# High_Side_FETs.net
KiCad netlist of a schematic drawn in Altium Designer
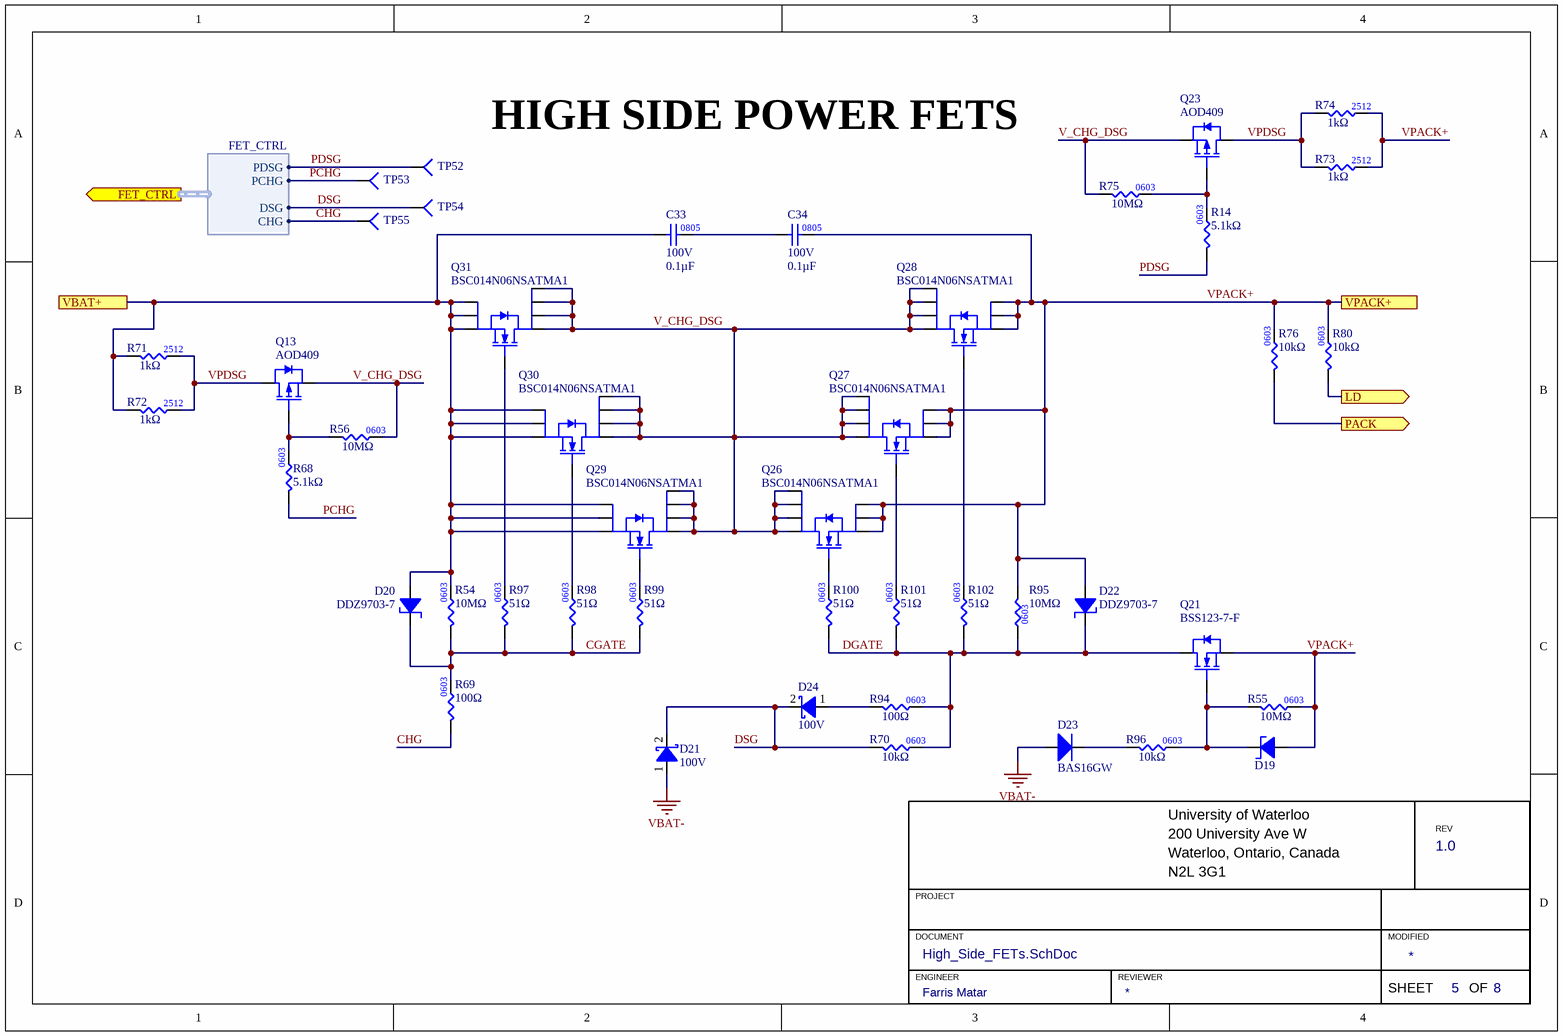
[diagram p0: High_Side_FETs.SchDoc]

(export (version "E")
  (design (tool "Eeschema 10.0.6"))
  (components
    (comp (ref "C33")
      (value "0.1µF")
      (footprint "CAP0805")
      (description "CAP CER 0.1UF 100V X7R 0805")
      (fields (field (name "VOLTAGE RATING") "100V") (field (name "Comment") "CAP_0.1uF_100V_0805"))
      (libsource (lib "Personal_Schematic_Library_2022") (part "CAP_0.1uF_100V_0805"))
    )
    (comp (ref "C34")
      (value "0.1µF")
      (footprint "CAP0805")
      (description "CAP CER 0.1UF 100V X7R 0805")
      (fields (field (name "VOLTAGE RATING") "100V") (field (name "Comment") "CAP_0.1uF_100V_0805"))
      (libsource (lib "Personal_Schematic_Library_2022") (part "CAP_0.1uF_100V_0805"))
    )
    (comp (ref "D19")
      (value "DIO_ZENER_16V")
      (footprint "SOD-123_FLAT")
      (description "DIODE ZENER 16V 500MW SOD123")
      (libsource (lib "Personal_Schematic_Library_2022") (part "DIO_ZENER_16V"))
    )
    (comp (ref "D20")
      (value "DIO_ZENER_16V")
      (footprint "SOD-123_FLAT")
      (description "DIODE ZENER 16V 500MW SOD123")
      (fields (field (name "MANUFACTURER PART NUMBER 1") "DDZ9703-7"))
      (libsource (lib "Personal_Schematic_Library_2022") (part "DIO_ZENER_16V"))
    )
    (comp (ref "D21")
      (value "DIO_SCHOTTKY_100V_1A")
      (footprint "SOD-123_FLAT")
      (description "DIODE SCHOTTKY 100V 1A SOD-123F")
      (fields (field (name "VR (MAX)") "100V"))
      (libsource (lib "Personal_Schematic_Library_2022") (part "DIO_SCHOTTKY_100V_1A"))
    )
    (comp (ref "D22")
      (value "DIO_ZENER_16V")
      (footprint "SOD-123_FLAT")
      (description "DIODE ZENER 16V 500MW SOD123")
      (fields (field (name "MANUFACTURER PART NUMBER 1") "DDZ9703-7"))
      (libsource (lib "Personal_Schematic_Library_2022") (part "DIO_ZENER_16V"))
    )
    (comp (ref "D23")
      (value "DIO_100V_215mA")
      (footprint "DIODSOD-123")
      (description "DIODE GEN PURP 100V 215MA SOD123")
      (fields (field (name "MANUFACTURER PART NUMBER 1") "BAS16GW"))
      (libsource (lib "Personal_Schematic_Library_2022") (part "DIO_100V_215mA"))
    )
    (comp (ref "D24")
      (value "DIO_SCHOTTKY_100V_1A")
      (footprint "SOD-123_FLAT")
      (description "DIODE SCHOTTKY 100V 1A SOD-123F")
      (fields (field (name "VR (MAX)") "100V"))
      (libsource (lib "Personal_Schematic_Library_2022") (part "DIO_SCHOTTKY_100V_1A"))
    )
    (comp (ref "Q13")
      (value "PMOS_60V_26A")
      (footprint "TO-252 AOSMD")
      (description "MOSFET P-CH 60V 26A TO252")
      (fields (field (name "MANUFACTURER PART NUMBER 1") "AOD409"))
      (libsource (lib "Personal_Schematic_Library_2022") (part "PMOS_60V_26A"))
    )
    (comp (ref "Q21")
      (value "NMOS_100V_170mA")
      (footprint "SOT23-3")
      (description "MOSFET N-CH 100V 170MA SOT23-3")
      (fields (field (name "MANUFACTURER PART NUMBER 1") "BSS123-7-F"))
      (libsource (lib "Personal_Schematic_Library_2022") (part "NMOS_100V_170mA"))
    )
    (comp (ref "Q23")
      (value "PMOS_60V_26A")
      (footprint "TO-252 AOSMD")
      (description "MOSFET P-CH 60V 26A TO252")
      (fields (field (name "MANUFACTURER PART NUMBER 1") "AOD409"))
      (libsource (lib "Personal_Schematic_Library_2022") (part "PMOS_60V_26A"))
    )
    (comp (ref "Q26")
      (value "NMOS_60V_30A")
      (footprint "INFINEON_8-POWERTDFN")
      (description "MOSFET N-CH 60V 30A/100A TDSON7")
      (fields (field (name "MANUFACTURER PART NUMBER 1") "BSC014N06NSATMA1"))
      (libsource (lib "Personal_Schematic_Library_2022") (part "NMOS_60V_30A"))
    )
    (comp (ref "Q27")
      (value "NMOS_60V_30A")
      (footprint "INFINEON_8-POWERTDFN")
      (description "MOSFET N-CH 60V 30A/100A TDSON7")
      (fields (field (name "MANUFACTURER PART NUMBER 1") "BSC014N06NSATMA1"))
      (libsource (lib "Personal_Schematic_Library_2022") (part "NMOS_60V_30A"))
    )
    (comp (ref "Q28")
      (value "NMOS_60V_30A")
      (footprint "INFINEON_8-POWERTDFN")
      (description "MOSFET N-CH 60V 30A/100A TDSON7")
      (fields (field (name "MANUFACTURER PART NUMBER 1") "BSC014N06NSATMA1"))
      (libsource (lib "Personal_Schematic_Library_2022") (part "NMOS_60V_30A"))
    )
    (comp (ref "Q29")
      (value "NMOS_60V_30A")
      (footprint "INFINEON_8-POWERTDFN")
      (description "MOSFET N-CH 60V 30A/100A TDSON7")
      (fields (field (name "MANUFACTURER PART NUMBER 1") "BSC014N06NSATMA1"))
      (libsource (lib "Personal_Schematic_Library_2022") (part "NMOS_60V_30A"))
    )
    (comp (ref "Q30")
      (value "NMOS_60V_30A")
      (footprint "INFINEON_8-POWERTDFN")
      (description "MOSFET N-CH 60V 30A/100A TDSON7")
      (fields (field (name "MANUFACTURER PART NUMBER 1") "BSC014N06NSATMA1"))
      (libsource (lib "Personal_Schematic_Library_2022") (part "NMOS_60V_30A"))
    )
    (comp (ref "Q31")
      (value "NMOS_60V_30A")
      (footprint "INFINEON_8-POWERTDFN")
      (description "MOSFET N-CH 60V 30A/100A TDSON7")
      (fields (field (name "MANUFACTURER PART NUMBER 1") "BSC014N06NSATMA1"))
      (libsource (lib "Personal_Schematic_Library_2022") (part "NMOS_60V_30A"))
    )
    (comp (ref "R14")
      (value "5.1kΩ")
      (footprint "RES0603")
      (description "RES 5.1K OHM 1% 1/10W 0603")
      (fields (field (name "Comment") "RES_5.1kΩ_0603_1%"))
      (libsource (lib "Personal_Schematic_Library_2022") (part "RES_5.1kΩ_0603_1%"))
    )
    (comp (ref "R54")
      (value "10MΩ")
      (footprint "RES0603")
      (description "RES 10M OHM 1% 1/10W 0603")
      (fields (field (name "Comment") "RES_10MΩ_0603_1%"))
      (libsource (lib "Personal_Schematic_Library_2022") (part "RES_10MΩ_0603_1%"))
    )
    (comp (ref "R55")
      (value "10MΩ")
      (footprint "RES0603")
      (description "RES 10M OHM 1% 1/10W 0603")
      (fields (field (name "Comment") "RES_10MΩ_0603_1%"))
      (libsource (lib "Personal_Schematic_Library_2022") (part "RES_10MΩ_0603_1%"))
    )
    (comp (ref "R56")
      (value "10MΩ")
      (footprint "RES0603")
      (description "RES 10M OHM 1% 1/10W 0603")
      (fields (field (name "Comment") "RES_10MΩ_0603_1%"))
      (libsource (lib "Personal_Schematic_Library_2022") (part "RES_10MΩ_0603_1%"))
    )
    (comp (ref "R68")
      (value "5.1kΩ")
      (footprint "RES0603")
      (description "RES 5.1K OHM 1% 1/10W 0603")
      (fields (field (name "Comment") "RES_5.1kΩ_0603_1%"))
      (libsource (lib "Personal_Schematic_Library_2022") (part "RES_5.1kΩ_0603_1%"))
    )
    (comp (ref "R69")
      (value "100Ω")
      (footprint "RES0603")
      (description "RES 100 OHM 1% 1/10W 0603")
      (fields (field (name "Comment") "RES_100Ω_0603_1%"))
      (libsource (lib "Personal_Schematic_Library_2022") (part "RES_100Ω_0603_1%"))
    )
    (comp (ref "R70")
      (value "10kΩ")
      (footprint "RES0603")
      (description "RES 10K OHM 1% 1/8W 0603")
      (fields (field (name "Comment") "RES_10kΩ_0603_1%"))
      (libsource (lib "Personal_Schematic_Library_2022") (part "RES_10kΩ_0603_1%"))
    )
    (comp (ref "R71")
      (value "1kΩ")
      (footprint "RES2512")
      (description "RES SMD 1K OHM 1% 3W 2512")
      (fields (field (name "Comment") "RES_1kΩ_2512_1%"))
      (libsource (lib "Personal_Schematic_Library_2022") (part "RES_1kΩ_2512_1%"))
    )
    (comp (ref "R72")
      (value "1kΩ")
      (footprint "RES2512")
      (description "RES SMD 1K OHM 1% 3W 2512")
      (fields (field (name "Comment") "RES_1kΩ_2512_1%"))
      (libsource (lib "Personal_Schematic_Library_2022") (part "RES_1kΩ_2512_1%"))
    )
    (comp (ref "R73")
      (value "1kΩ")
      (footprint "RES2512")
      (description "RES SMD 1K OHM 1% 3W 2512")
      (fields (field (name "Comment") "RES_1kΩ_2512_1%"))
      (libsource (lib "Personal_Schematic_Library_2022") (part "RES_1kΩ_2512_1%"))
    )
    (comp (ref "R74")
      (value "1kΩ")
      (footprint "RES2512")
      (description "RES SMD 1K OHM 1% 3W 2512")
      (fields (field (name "Comment") "RES_1kΩ_2512_1%"))
      (libsource (lib "Personal_Schematic_Library_2022") (part "RES_1kΩ_2512_1%"))
    )
    (comp (ref "R75")
      (value "10MΩ")
      (footprint "RES0603")
      (description "RES 10M OHM 1% 1/10W 0603")
      (fields (field (name "Comment") "RES_10MΩ_0603_1%"))
      (libsource (lib "Personal_Schematic_Library_2022") (part "RES_10MΩ_0603_1%"))
    )
    (comp (ref "R76")
      (value "10kΩ")
      (footprint "RES0603")
      (description "RES 10K OHM 1% 1/8W 0603")
      (fields (field (name "Comment") "RES_10kΩ_0603_1%"))
      (libsource (lib "Personal_Schematic_Library_2022") (part "RES_10kΩ_0603_1%"))
    )
    (comp (ref "R80")
      (value "10kΩ")
      (footprint "RES0603")
      (description "RES 10K OHM 1% 1/8W 0603")
      (fields (field (name "Comment") "RES_10kΩ_0603_1%"))
      (libsource (lib "Personal_Schematic_Library_2022") (part "RES_10kΩ_0603_1%"))
    )
    (comp (ref "R94")
      (value "100Ω")
      (footprint "RES0603")
      (description "RES 100 OHM 1% 1/10W 0603")
      (fields (field (name "Comment") "RES_100Ω_0603_1%"))
      (libsource (lib "Personal_Schematic_Library_2022") (part "RES_100Ω_0603_1%"))
    )
    (comp (ref "R95")
      (value "10MΩ")
      (footprint "RES0603")
      (description "RES 10M OHM 1% 1/10W 0603")
      (fields (field (name "Comment") "RES_10MΩ_0603_1%"))
      (libsource (lib "Personal_Schematic_Library_2022") (part "RES_10MΩ_0603_1%"))
    )
    (comp (ref "R96")
      (value "10kΩ")
      (footprint "RES0603")
      (description "RES 10K OHM 1% 1/8W 0603")
      (fields (field (name "Comment") "RES_10kΩ_0603_1%"))
      (libsource (lib "Personal_Schematic_Library_2022") (part "RES_10kΩ_0603_1%"))
    )
    (comp (ref "R97")
      (value "51Ω")
      (footprint "RES0603")
      (description "RES 51 OHM 1% 1/10W 0603")
      (fields (field (name "Comment") "RES_51Ω_0603_1%"))
      (libsource (lib "Personal_Schematic_Library_2022") (part "RES_51Ω_0603_1%"))
    )
    (comp (ref "R98")
      (value "51Ω")
      (footprint "RES0603")
      (description "RES 51 OHM 1% 1/10W 0603")
      (fields (field (name "Comment") "RES_51Ω_0603_1%"))
      (libsource (lib "Personal_Schematic_Library_2022") (part "RES_51Ω_0603_1%"))
    )
    (comp (ref "R99")
      (value "51Ω")
      (footprint "RES0603")
      (description "RES 51 OHM 1% 1/10W 0603")
      (fields (field (name "Comment") "RES_51Ω_0603_1%"))
      (libsource (lib "Personal_Schematic_Library_2022") (part "RES_51Ω_0603_1%"))
    )
    (comp (ref "R100")
      (value "51Ω")
      (footprint "RES0603")
      (description "RES 51 OHM 1% 1/10W 0603")
      (fields (field (name "Comment") "RES_51Ω_0603_1%"))
      (libsource (lib "Personal_Schematic_Library_2022") (part "RES_51Ω_0603_1%"))
    )
    (comp (ref "R101")
      (value "51Ω")
      (footprint "RES0603")
      (description "RES 51 OHM 1% 1/10W 0603")
      (fields (field (name "Comment") "RES_51Ω_0603_1%"))
      (libsource (lib "Personal_Schematic_Library_2022") (part "RES_51Ω_0603_1%"))
    )
    (comp (ref "R102")
      (value "51Ω")
      (footprint "RES0603")
      (description "RES 51 OHM 1% 1/10W 0603")
      (fields (field (name "Comment") "RES_51Ω_0603_1%"))
      (libsource (lib "Personal_Schematic_Library_2022") (part "RES_51Ω_0603_1%"))
    )
    (comp (ref "TP52")
      (value "TESTPOINT_1MM_CIRCLE")
      (footprint "TESTPOINT_CIRCLE_1MM")
      (description "TESTPOINT 1MM CIRCLE")
      (libsource (lib "Personal_Schematic_Library_2022") (part "TESTPOINT_1MM_CIRCLE"))
    )
    (comp (ref "TP53")
      (value "TESTPOINT_1MM_CIRCLE")
      (footprint "TESTPOINT_CIRCLE_1MM")
      (description "TESTPOINT 1MM CIRCLE")
      (libsource (lib "Personal_Schematic_Library_2022") (part "TESTPOINT_1MM_CIRCLE"))
    )
    (comp (ref "TP54")
      (value "TESTPOINT_1MM_CIRCLE")
      (footprint "TESTPOINT_CIRCLE_1MM")
      (description "TESTPOINT 1MM CIRCLE")
      (libsource (lib "Personal_Schematic_Library_2022") (part "TESTPOINT_1MM_CIRCLE"))
    )
    (comp (ref "TP55")
      (value "TESTPOINT_1MM_CIRCLE")
      (footprint "TESTPOINT_CIRCLE_1MM")
      (description "TESTPOINT 1MM CIRCLE")
      (libsource (lib "Personal_Schematic_Library_2022") (part "TESTPOINT_1MM_CIRCLE"))
    )
  )
  (nets
    (net (code "2") (name "/CGATE") (class "Default")
      (node (ref "D20") (pin "2") (pinfunction "Cathode_2") (pintype "passive"))
      (node (ref "R54") (pin "1") (pinfunction "1_1") (pintype "passive"))
      (node (ref "R69") (pin "2") (pinfunction "2_2") (pintype "passive"))
      (node (ref "R97") (pin "1") (pinfunction "1_1") (pintype "passive"))
      (node (ref "R98") (pin "1") (pinfunction "1_1") (pintype "passive"))
      (node (ref "R99") (pin "1") (pinfunction "1_1") (pintype "passive"))
    )
    (net (code "3") (name "/CHG") (class "Default")
      (node (ref "R69") (pin "1") (pinfunction "1_1") (pintype "passive"))
      (node (ref "TP55") (pin "1") (pinfunction "=value_1") (pintype "passive"))
    )
    (net (code "4") (name "/DGATE") (class "Default")
      (node (ref "D22") (pin "2") (pinfunction "Cathode_2") (pintype "passive"))
      (node (ref "Q21") (pin "3") (pinfunction "DRAIN_3") (pintype "passive"))
      (node (ref "R100") (pin "1") (pinfunction "1_1") (pintype "passive"))
      (node (ref "R101") (pin "1") (pinfunction "1_1") (pintype "passive"))
      (node (ref "R102") (pin "1") (pinfunction "1_1") (pintype "passive"))
      (node (ref "R70") (pin "2") (pinfunction "2_2") (pintype "passive"))
      (node (ref "R94") (pin "2") (pinfunction "2_2") (pintype "passive"))
      (node (ref "R95") (pin "1") (pinfunction "1_1") (pintype "passive"))
    )
    (net (code "5") (name "/DSG") (class "Default")
      (node (ref "D21") (pin "2") (pinfunction "Cathode_2") (pintype "passive"))
      (node (ref "D24") (pin "2") (pinfunction "Cathode_2") (pintype "passive"))
      (node (ref "R70") (pin "1") (pinfunction "1_1") (pintype "passive"))
      (node (ref "TP54") (pin "1") (pinfunction "=value_1") (pintype "passive"))
    )
    (net (code "6") (name "/LD") (class "Default")
      (node (ref "R80") (pin "1") (pinfunction "1_1") (pintype "passive"))
    )
    (net (code "7") (name "/PACK") (class "Default")
      (node (ref "R76") (pin "1") (pinfunction "1_1") (pintype "passive"))
    )
    (net (code "8") (name "/PCHG") (class "Default")
      (node (ref "R68") (pin "1") (pinfunction "1_1") (pintype "passive"))
      (node (ref "TP53") (pin "1") (pinfunction "=value_1") (pintype "passive"))
    )
    (net (code "9") (name "/PDSG") (class "Default")
      (node (ref "R14") (pin "1") (pinfunction "1_1") (pintype "passive"))
      (node (ref "TP52") (pin "1") (pinfunction "=value_1") (pintype "passive"))
    )
    (net (code "10") (name "/VBAT+") (class "Default")
      (node (ref "C33") (pin "1") (pinfunction "1_1") (pintype "passive"))
      (node (ref "D20") (pin "1") (pinfunction "Anode_1") (pintype "passive"))
      (node (ref "Q29") (pin "1") (pinfunction "Source_1") (pintype "passive"))
      (node (ref "Q29") (pin "2") (pinfunction "Source_2") (pintype "passive"))
      (node (ref "Q29") (pin "3") (pinfunction "Source_3") (pintype "passive"))
      (node (ref "Q30") (pin "1") (pinfunction "Source_1") (pintype "passive"))
      (node (ref "Q30") (pin "2") (pinfunction "Source_2") (pintype "passive"))
      (node (ref "Q30") (pin "3") (pinfunction "Source_3") (pintype "passive"))
      (node (ref "Q31") (pin "1") (pinfunction "Source_1") (pintype "passive"))
      (node (ref "Q31") (pin "2") (pinfunction "Source_2") (pintype "passive"))
      (node (ref "Q31") (pin "3") (pinfunction "Source_3") (pintype "passive"))
      (node (ref "R54") (pin "2") (pinfunction "2_2") (pintype "passive"))
      (node (ref "R71") (pin "1") (pinfunction "1_1") (pintype "passive"))
      (node (ref "R72") (pin "1") (pinfunction "1_1") (pintype "passive"))
    )
    (net (code "11") (name "/VPACK+") (class "Default")
      (node (ref "C34") (pin "2") (pinfunction "2_2") (pintype "passive"))
      (node (ref "D19") (pin "1") (pinfunction "Anode_1") (pintype "passive"))
      (node (ref "D22") (pin "1") (pinfunction "Anode_1") (pintype "passive"))
      (node (ref "Q21") (pin "2") (pinfunction "SOURCE_2") (pintype "passive"))
      (node (ref "Q26") (pin "1") (pinfunction "Source_1") (pintype "passive"))
      (node (ref "Q26") (pin "2") (pinfunction "Source_2") (pintype "passive"))
      (node (ref "Q26") (pin "3") (pinfunction "Source_3") (pintype "passive"))
      (node (ref "Q27") (pin "1") (pinfunction "Source_1") (pintype "passive"))
      (node (ref "Q27") (pin "2") (pinfunction "Source_2") (pintype "passive"))
      (node (ref "Q27") (pin "3") (pinfunction "Source_3") (pintype "passive"))
      (node (ref "Q28") (pin "1") (pinfunction "Source_1") (pintype "passive"))
      (node (ref "Q28") (pin "2") (pinfunction "Source_2") (pintype "passive"))
      (node (ref "Q28") (pin "3") (pinfunction "Source_3") (pintype "passive"))
      (node (ref "R55") (pin "2") (pinfunction "2_2") (pintype "passive"))
      (node (ref "R73") (pin "2") (pinfunction "2_2") (pintype "passive"))
      (node (ref "R74") (pin "2") (pinfunction "2_2") (pintype "passive"))
      (node (ref "R76") (pin "2") (pinfunction "2_2") (pintype "passive"))
      (node (ref "R80") (pin "2") (pinfunction "2_2") (pintype "passive"))
      (node (ref "R95") (pin "2") (pinfunction "2_2") (pintype "passive"))
    )
    (net (code "12") (name "/VPDSG") (class "Default")
      (node (ref "Q13") (pin "2") (pinfunction "Drain_2") (pintype "passive"))
      (node (ref "Q23") (pin "2") (pinfunction "Drain_2") (pintype "passive"))
      (node (ref "R71") (pin "2") (pinfunction "2_2") (pintype "passive"))
      (node (ref "R72") (pin "2") (pinfunction "2_2") (pintype "passive"))
      (node (ref "R73") (pin "1") (pinfunction "1_1") (pintype "passive"))
      (node (ref "R74") (pin "1") (pinfunction "1_1") (pintype "passive"))
    )
    (net (code "13") (name "/V_CHG_DSG") (class "Default")
      (node (ref "Q13") (pin "3") (pinfunction "Source_3") (pintype "passive"))
      (node (ref "Q23") (pin "3") (pinfunction "Source_3") (pintype "passive"))
      (node (ref "Q26") (pin "5") (pinfunction "Drain_5") (pintype "passive"))
      (node (ref "Q26") (pin "6") (pinfunction "Drain_6") (pintype "passive"))
      (node (ref "Q26") (pin "7") (pinfunction "Drain_7") (pintype "passive"))
      (node (ref "Q26") (pin "8") (pinfunction "Drain_8") (pintype "passive"))
      (node (ref "Q27") (pin "5") (pinfunction "Drain_5") (pintype "passive"))
      (node (ref "Q27") (pin "6") (pinfunction "Drain_6") (pintype "passive"))
      (node (ref "Q27") (pin "7") (pinfunction "Drain_7") (pintype "passive"))
      (node (ref "Q27") (pin "8") (pinfunction "Drain_8") (pintype "passive"))
      (node (ref "Q28") (pin "5") (pinfunction "Drain_5") (pintype "passive"))
      (node (ref "Q28") (pin "6") (pinfunction "Drain_6") (pintype "passive"))
      (node (ref "Q28") (pin "7") (pinfunction "Drain_7") (pintype "passive"))
      (node (ref "Q28") (pin "8") (pinfunction "Drain_8") (pintype "passive"))
      (node (ref "Q29") (pin "5") (pinfunction "Drain_5") (pintype "passive"))
      (node (ref "Q29") (pin "6") (pinfunction "Drain_6") (pintype "passive"))
      (node (ref "Q29") (pin "7") (pinfunction "Drain_7") (pintype "passive"))
      (node (ref "Q29") (pin "8") (pinfunction "Drain_8") (pintype "passive"))
      (node (ref "Q30") (pin "5") (pinfunction "Drain_5") (pintype "passive"))
      (node (ref "Q30") (pin "6") (pinfunction "Drain_6") (pintype "passive"))
      (node (ref "Q30") (pin "7") (pinfunction "Drain_7") (pintype "passive"))
      (node (ref "Q30") (pin "8") (pinfunction "Drain_8") (pintype "passive"))
      (node (ref "Q31") (pin "5") (pinfunction "Drain_5") (pintype "passive"))
      (node (ref "Q31") (pin "6") (pinfunction "Drain_6") (pintype "passive"))
      (node (ref "Q31") (pin "7") (pinfunction "Drain_7") (pintype "passive"))
      (node (ref "Q31") (pin "8") (pinfunction "Drain_8") (pintype "passive"))
      (node (ref "R56") (pin "2") (pinfunction "2_2") (pintype "passive"))
      (node (ref "R75") (pin "1") (pinfunction "1_1") (pintype "passive"))
    )
    (net (code "15") (name "Net-(C33-Pad2)") (class "Default")
      (node (ref "C33") (pin "2") (pinfunction "2_2") (pintype "passive"))
      (node (ref "C34") (pin "1") (pinfunction "1_1") (pintype "passive"))
    )
    (net (code "16") (name "Net-(D19-Cathode)") (class "Default")
      (node (ref "D19") (pin "2") (pinfunction "Cathode_2") (pintype "passive"))
      (node (ref "Q21") (pin "1") (pinfunction "GATE_1") (pintype "passive"))
      (node (ref "R55") (pin "1") (pinfunction "1_1") (pintype "passive"))
      (node (ref "R96") (pin "2") (pinfunction "2_2") (pintype "passive"))
    )
    (net (code "17") (name "Net-(D23-K)") (class "Default")
      (node (ref "D23") (pin "2") (pinfunction "K_2") (pintype "passive"))
      (node (ref "R96") (pin "1") (pinfunction "1_1") (pintype "passive"))
    )
    (net (code "18") (name "Net-(D24-Anode)") (class "Default")
      (node (ref "D24") (pin "1") (pinfunction "Anode_1") (pintype "passive"))
      (node (ref "R94") (pin "1") (pinfunction "1_1") (pintype "passive"))
    )
    (net (code "19") (name "Net-(Q13-Gate)") (class "Default")
      (node (ref "Q13") (pin "1") (pinfunction "Gate_1") (pintype "passive"))
      (node (ref "R56") (pin "1") (pinfunction "1_1") (pintype "passive"))
      (node (ref "R68") (pin "2") (pinfunction "2_2") (pintype "passive"))
    )
    (net (code "20") (name "Net-(Q23-Gate)") (class "Default")
      (node (ref "Q23") (pin "1") (pinfunction "Gate_1") (pintype "passive"))
      (node (ref "R14") (pin "2") (pinfunction "2_2") (pintype "passive"))
      (node (ref "R75") (pin "2") (pinfunction "2_2") (pintype "passive"))
    )
    (net (code "21") (name "Net-(Q26-Gate)") (class "Default")
      (node (ref "Q26") (pin "4") (pinfunction "Gate_4") (pintype "passive"))
      (node (ref "R100") (pin "2") (pinfunction "2_2") (pintype "passive"))
    )
    (net (code "22") (name "Net-(Q27-Gate)") (class "Default")
      (node (ref "Q27") (pin "4") (pinfunction "Gate_4") (pintype "passive"))
      (node (ref "R101") (pin "2") (pinfunction "2_2") (pintype "passive"))
    )
    (net (code "23") (name "Net-(Q28-Gate)") (class "Default")
      (node (ref "Q28") (pin "4") (pinfunction "Gate_4") (pintype "passive"))
      (node (ref "R102") (pin "2") (pinfunction "2_2") (pintype "passive"))
    )
    (net (code "24") (name "Net-(Q29-Gate)") (class "Default")
      (node (ref "Q29") (pin "4") (pinfunction "Gate_4") (pintype "passive"))
      (node (ref "R99") (pin "2") (pinfunction "2_2") (pintype "passive"))
    )
    (net (code "25") (name "Net-(Q30-Gate)") (class "Default")
      (node (ref "Q30") (pin "4") (pinfunction "Gate_4") (pintype "passive"))
      (node (ref "R98") (pin "2") (pinfunction "2_2") (pintype "passive"))
    )
    (net (code "26") (name "Net-(Q31-Gate)") (class "Default")
      (node (ref "Q31") (pin "4") (pinfunction "Gate_4") (pintype "passive"))
      (node (ref "R97") (pin "2") (pinfunction "2_2") (pintype "passive"))
    )
    (net (code "27") (name "VBAT-") (class "Default")
      (node (ref "D21") (pin "1") (pinfunction "Anode_1") (pintype "passive"))
      (node (ref "D23") (pin "1") (pinfunction "A_1") (pintype "passive"))
    )
  )
)
